# SCH_Waterloo-Project_2025-10-19.net
KiCad netlist of a schematic drawn in EasyEDA
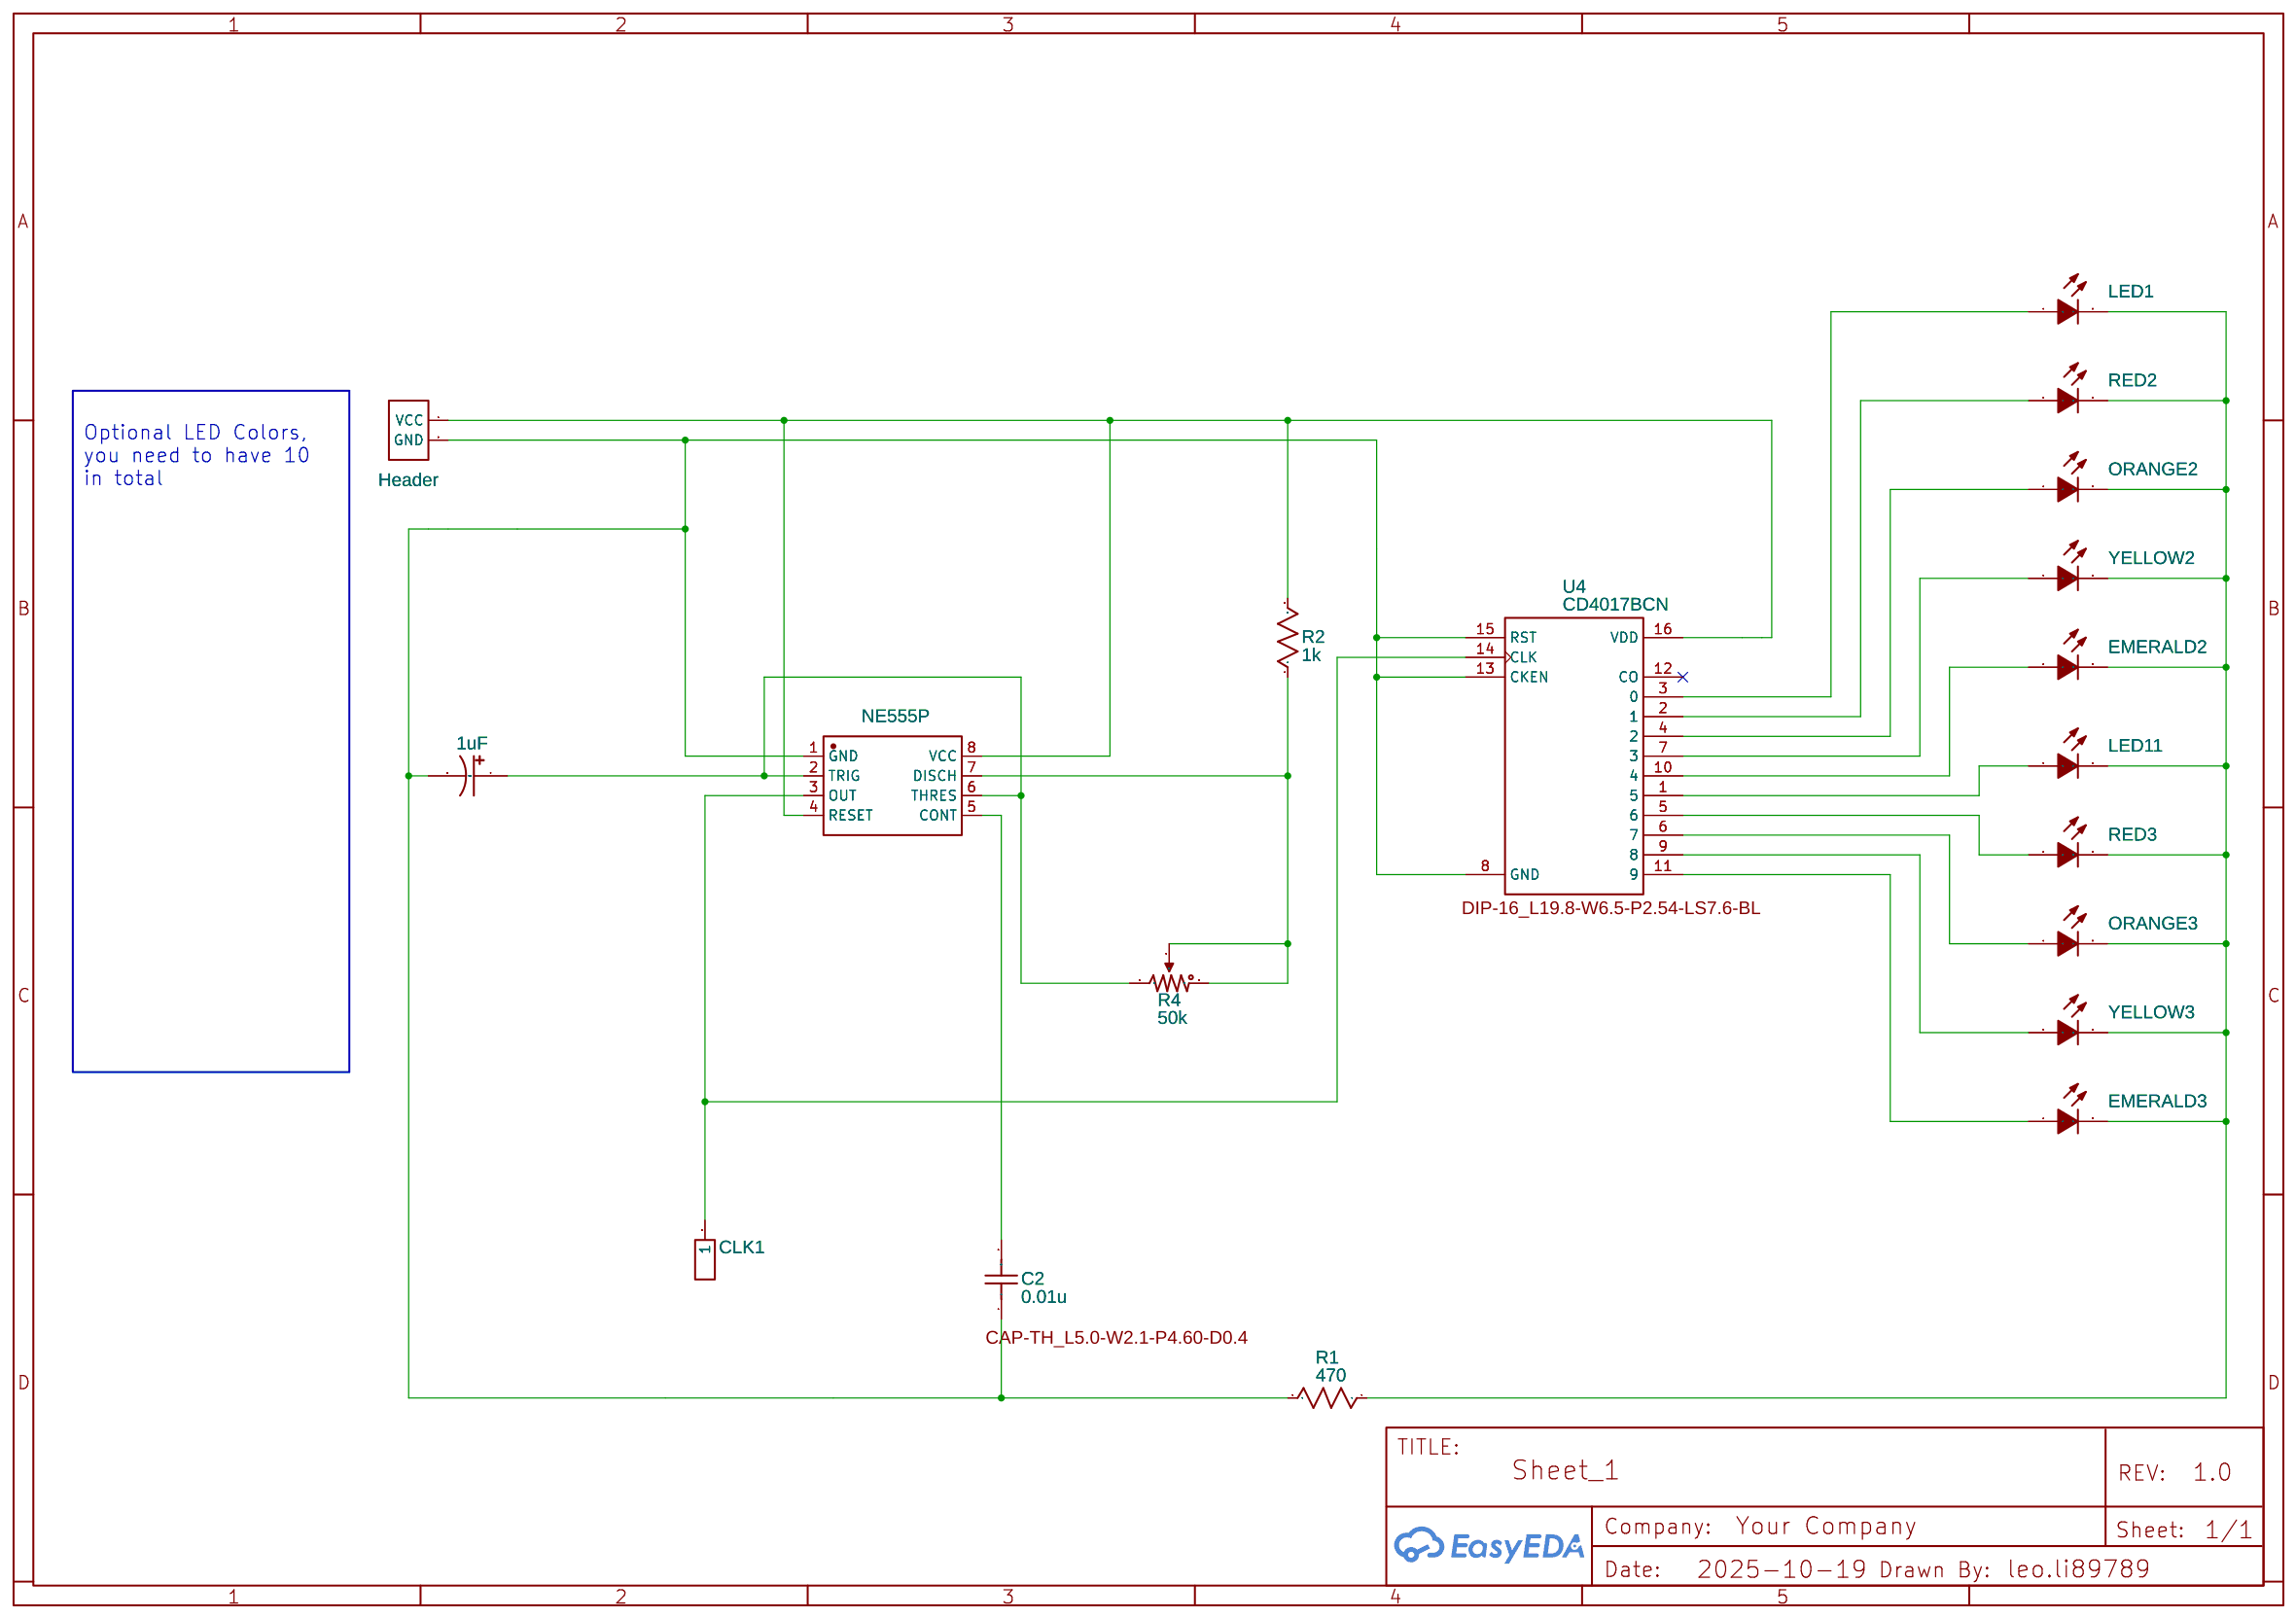
[diagram p0: schematic sheet]

(export (version "E")
  (design (tool "Eeschema 10.0.6"))
  (components
    (comp (ref "C1")
      (value "1uF")
      (fields (field (name "Manufacturer Part") "UVZ1H010MDD") (field (name "Manufacturer") "Nichicon(尼吉康)"))
      (libsource (lib "") (part "UVZ1H010MDD"))
    )
    (comp (ref "C2") (value "0.01u") (libsource (lib "") (part "C_0603_US")))
    (comp (ref "CLK1")
      (value "C81276")
      (fields
        (field (name "Manufacturer Part") "2.54-1*1P针")
        (field (name "Manufacturer") "BOOMELE(Boom Precision Elec)")
      )
      (libsource (lib "") (part "Header-Male-2.54_1x1"))
    )
    (comp (ref "EMERALD2") (value "LED_5MM") (libsource (lib "") (part "LED_5MM_1")))
    (comp (ref "EMERALD3") (value "LED_5MM") (libsource (lib "") (part "LED_5MM_1")))
    (comp (ref "H1") (value "Header") (libsource (lib "") (part "HEADER-FEMALE-2.54_1X2")))
    (comp (ref "LED1") (value "LED_5MM") (libsource (lib "") (part "LED_5MM_3")))
    (comp (ref "LED11") (value "LED_5MM") (libsource (lib "") (part "LED_5MM_3")))
    (comp (ref "ORANGE2") (value "LED_5MM") (libsource (lib "") (part "LED_5MM")))
    (comp (ref "ORANGE3") (value "LED_5MM") (libsource (lib "") (part "LED_5MM")))
    (comp (ref "R1")
      (value "470")
      (fields (field (name "Manufacturer Part") "?"))
      (libsource (lib "") (part "Resistor_1"))
    )
    (comp (ref "R2")
      (value "1k")
      (fields (field (name "Manufacturer Part") "?"))
      (libsource (lib "") (part "Resistor"))
    )
    (comp (ref "R4")
      (value "50k")
      (fields (field (name "Manufacturer Part") "?"))
      (libsource (lib "") (part "Potentiometer"))
    )
    (comp (ref "RED2") (value "LED_5MM") (libsource (lib "") (part "LED_5MM_2")))
    (comp (ref "RED3") (value "LED_5MM") (libsource (lib "") (part "LED_5MM_2")))
    (comp (ref "U2")
      (value "NE555P")
      (fields (field (name "Manufacturer") "TI(德州仪器)"))
      (libsource (lib "") (part "NE555P"))
    )
    (comp (ref "U4") (value "CD4017BCN") (libsource (lib "") (part "CD4017BCN")))
    (comp (ref "YELLOW2") (value "LED_5MM") (libsource (lib "") (part "LED_5MM_4")))
    (comp (ref "YELLOW3") (value "LED_5MM") (libsource (lib "") (part "LED_5MM_4")))
  )
  (nets
    (net (code "1") (name "Net-(EMERALD2-A)") (class "Default")
      (node (ref "EMERALD2") (pin "1") (pinfunction "A_1") (pintype "input"))
      (node (ref "U4") (pin "10") (pinfunction "4_10") (pintype "output"))
    )
    (net (code "2") (name "Net-(EMERALD2-K)") (class "Default")
      (node (ref "EMERALD2") (pin "2") (pinfunction "K_2") (pintype "input"))
      (node (ref "EMERALD3") (pin "2") (pinfunction "K_2") (pintype "input"))
      (node (ref "LED1") (pin "2") (pinfunction "K_2") (pintype "input"))
      (node (ref "LED11") (pin "2") (pinfunction "K_2") (pintype "input"))
      (node (ref "ORANGE2") (pin "2") (pinfunction "K_2") (pintype "input"))
      (node (ref "ORANGE3") (pin "2") (pinfunction "K_2") (pintype "input"))
      (node (ref "R1") (pin "1") (pinfunction "1_1") (pintype "unspecified"))
      (node (ref "RED2") (pin "2") (pinfunction "K_2") (pintype "input"))
      (node (ref "RED3") (pin "2") (pinfunction "K_2") (pintype "input"))
      (node (ref "YELLOW2") (pin "2") (pinfunction "K_2") (pintype "input"))
      (node (ref "YELLOW3") (pin "2") (pinfunction "K_2") (pintype "input"))
    )
    (net (code "3") (name "Net-(EMERALD3-A)") (class "Default")
      (node (ref "EMERALD3") (pin "1") (pinfunction "A_1") (pintype "input"))
      (node (ref "U4") (pin "11") (pinfunction "9_11") (pintype "output"))
    )
    (net (code "4") (name "Net-(H1-GND)") (class "Default")
      (node (ref "C1") (pin "2") (pinfunction "2_2") (pintype "unspecified"))
      (node (ref "C2") (pin "1") (pinfunction "1_1") (pintype "unspecified"))
      (node (ref "H1") (pin "2") (pinfunction "GND_2") (pintype "unspecified"))
      (node (ref "R1") (pin "2") (pinfunction "2_2") (pintype "unspecified"))
      (node (ref "U2") (pin "1") (pinfunction "GND_1") (pintype "unspecified"))
      (node (ref "U4") (pin "13") (pinfunction "CKEN_13") (pintype "unspecified"))
      (node (ref "U4") (pin "15") (pinfunction "RST_15") (pintype "unspecified"))
      (node (ref "U4") (pin "8") (pinfunction "GND_8") (pintype "passive"))
    )
    (net (code "5") (name "Net-(H1-VCC)") (class "Default")
      (node (ref "H1") (pin "1") (pinfunction "VCC_1") (pintype "unspecified"))
      (node (ref "R2") (pin "2") (pinfunction "2_2") (pintype "unspecified"))
      (node (ref "U2") (pin "4") (pinfunction "RESET_4") (pintype "unspecified"))
      (node (ref "U2") (pin "8") (pinfunction "VCC_8") (pintype "unspecified"))
      (node (ref "U4") (pin "16") (pinfunction "VDD_16") (pintype "passive"))
    )
    (net (code "6") (name "Net-(LED1-A)") (class "Default")
      (node (ref "LED1") (pin "1") (pinfunction "A_1") (pintype "input"))
      (node (ref "U4") (pin "3") (pinfunction "0_3") (pintype "output"))
    )
    (net (code "7") (name "Net-(LED11-A)") (class "Default")
      (node (ref "LED11") (pin "1") (pinfunction "A_1") (pintype "input"))
      (node (ref "U4") (pin "1") (pinfunction "5_1") (pintype "output"))
    )
    (net (code "8") (name "Net-(ORANGE2-A)") (class "Default")
      (node (ref "ORANGE2") (pin "1") (pinfunction "A_1") (pintype "input"))
      (node (ref "U4") (pin "4") (pinfunction "2_4") (pintype "output"))
    )
    (net (code "9") (name "Net-(ORANGE3-A)") (class "Default")
      (node (ref "ORANGE3") (pin "1") (pinfunction "A_1") (pintype "input"))
      (node (ref "U4") (pin "6") (pinfunction "7_6") (pintype "output"))
    )
    (net (code "10") (name "Net-(R4-2)") (class "Default")
      (node (ref "R2") (pin "1") (pinfunction "1_1") (pintype "unspecified"))
      (node (ref "R4") (pin "2") (pinfunction "3_2") (pintype "unspecified"))
      (node (ref "R4") (pin "3") (pinfunction "2_3") (pintype "unspecified"))
      (node (ref "U2") (pin "7") (pinfunction "DISCH_7") (pintype "unspecified"))
    )
    (net (code "11") (name "Net-(RED2-A)") (class "Default")
      (node (ref "RED2") (pin "1") (pinfunction "A_1") (pintype "input"))
      (node (ref "U4") (pin "2") (pinfunction "1_2") (pintype "output"))
    )
    (net (code "12") (name "Net-(RED3-A)") (class "Default")
      (node (ref "RED3") (pin "1") (pinfunction "A_1") (pintype "input"))
      (node (ref "U4") (pin "5") (pinfunction "6_5") (pintype "output"))
    )
    (net (code "13") (name "Net-(U2-CONT)") (class "Default")
      (node (ref "C2") (pin "2") (pinfunction "2_2") (pintype "unspecified"))
      (node (ref "U2") (pin "5") (pinfunction "CONT_5") (pintype "unspecified"))
    )
    (net (code "14") (name "Net-(U2-OUT)") (class "Default")
      (node (ref "CLK1") (pin "1") (pinfunction "1_1") (pintype "unspecified"))
      (node (ref "U2") (pin "3") (pinfunction "OUT_3") (pintype "unspecified"))
      (node (ref "U4") (pin "14") (pinfunction "CLK_14") (pintype "unspecified"))
    )
    (net (code "15") (name "Net-(U2-THRES)") (class "Default")
      (node (ref "C1") (pin "1") (pinfunction "1_1") (pintype "unspecified"))
      (node (ref "R4") (pin "1") (pinfunction "1_1") (pintype "unspecified"))
      (node (ref "U2") (pin "2") (pinfunction "TRIG_2") (pintype "unspecified"))
      (node (ref "U2") (pin "6") (pinfunction "THRES_6") (pintype "unspecified"))
    )
    (net (code "16") (name "Net-(U4-3)") (class "Default")
      (node (ref "U4") (pin "7") (pinfunction "3_7") (pintype "output"))
      (node (ref "YELLOW2") (pin "1") (pinfunction "A_1") (pintype "input"))
    )
    (net (code "17") (name "Net-(U4-8)") (class "Default")
      (node (ref "U4") (pin "9") (pinfunction "8_9") (pintype "output"))
      (node (ref "YELLOW3") (pin "1") (pinfunction "A_1") (pintype "input"))
    )
    (net (code "18") (name "unconnected-(U4-CO-Pad12)") (class "Default")
      (node (ref "U4") (pin "12") (pinfunction "CO_12") (pintype "output+no_connect"))
    )
  )
)
